# SCH_timer555_2026-08-26.net
KiCad netlist of a schematic drawn in EasyEDA
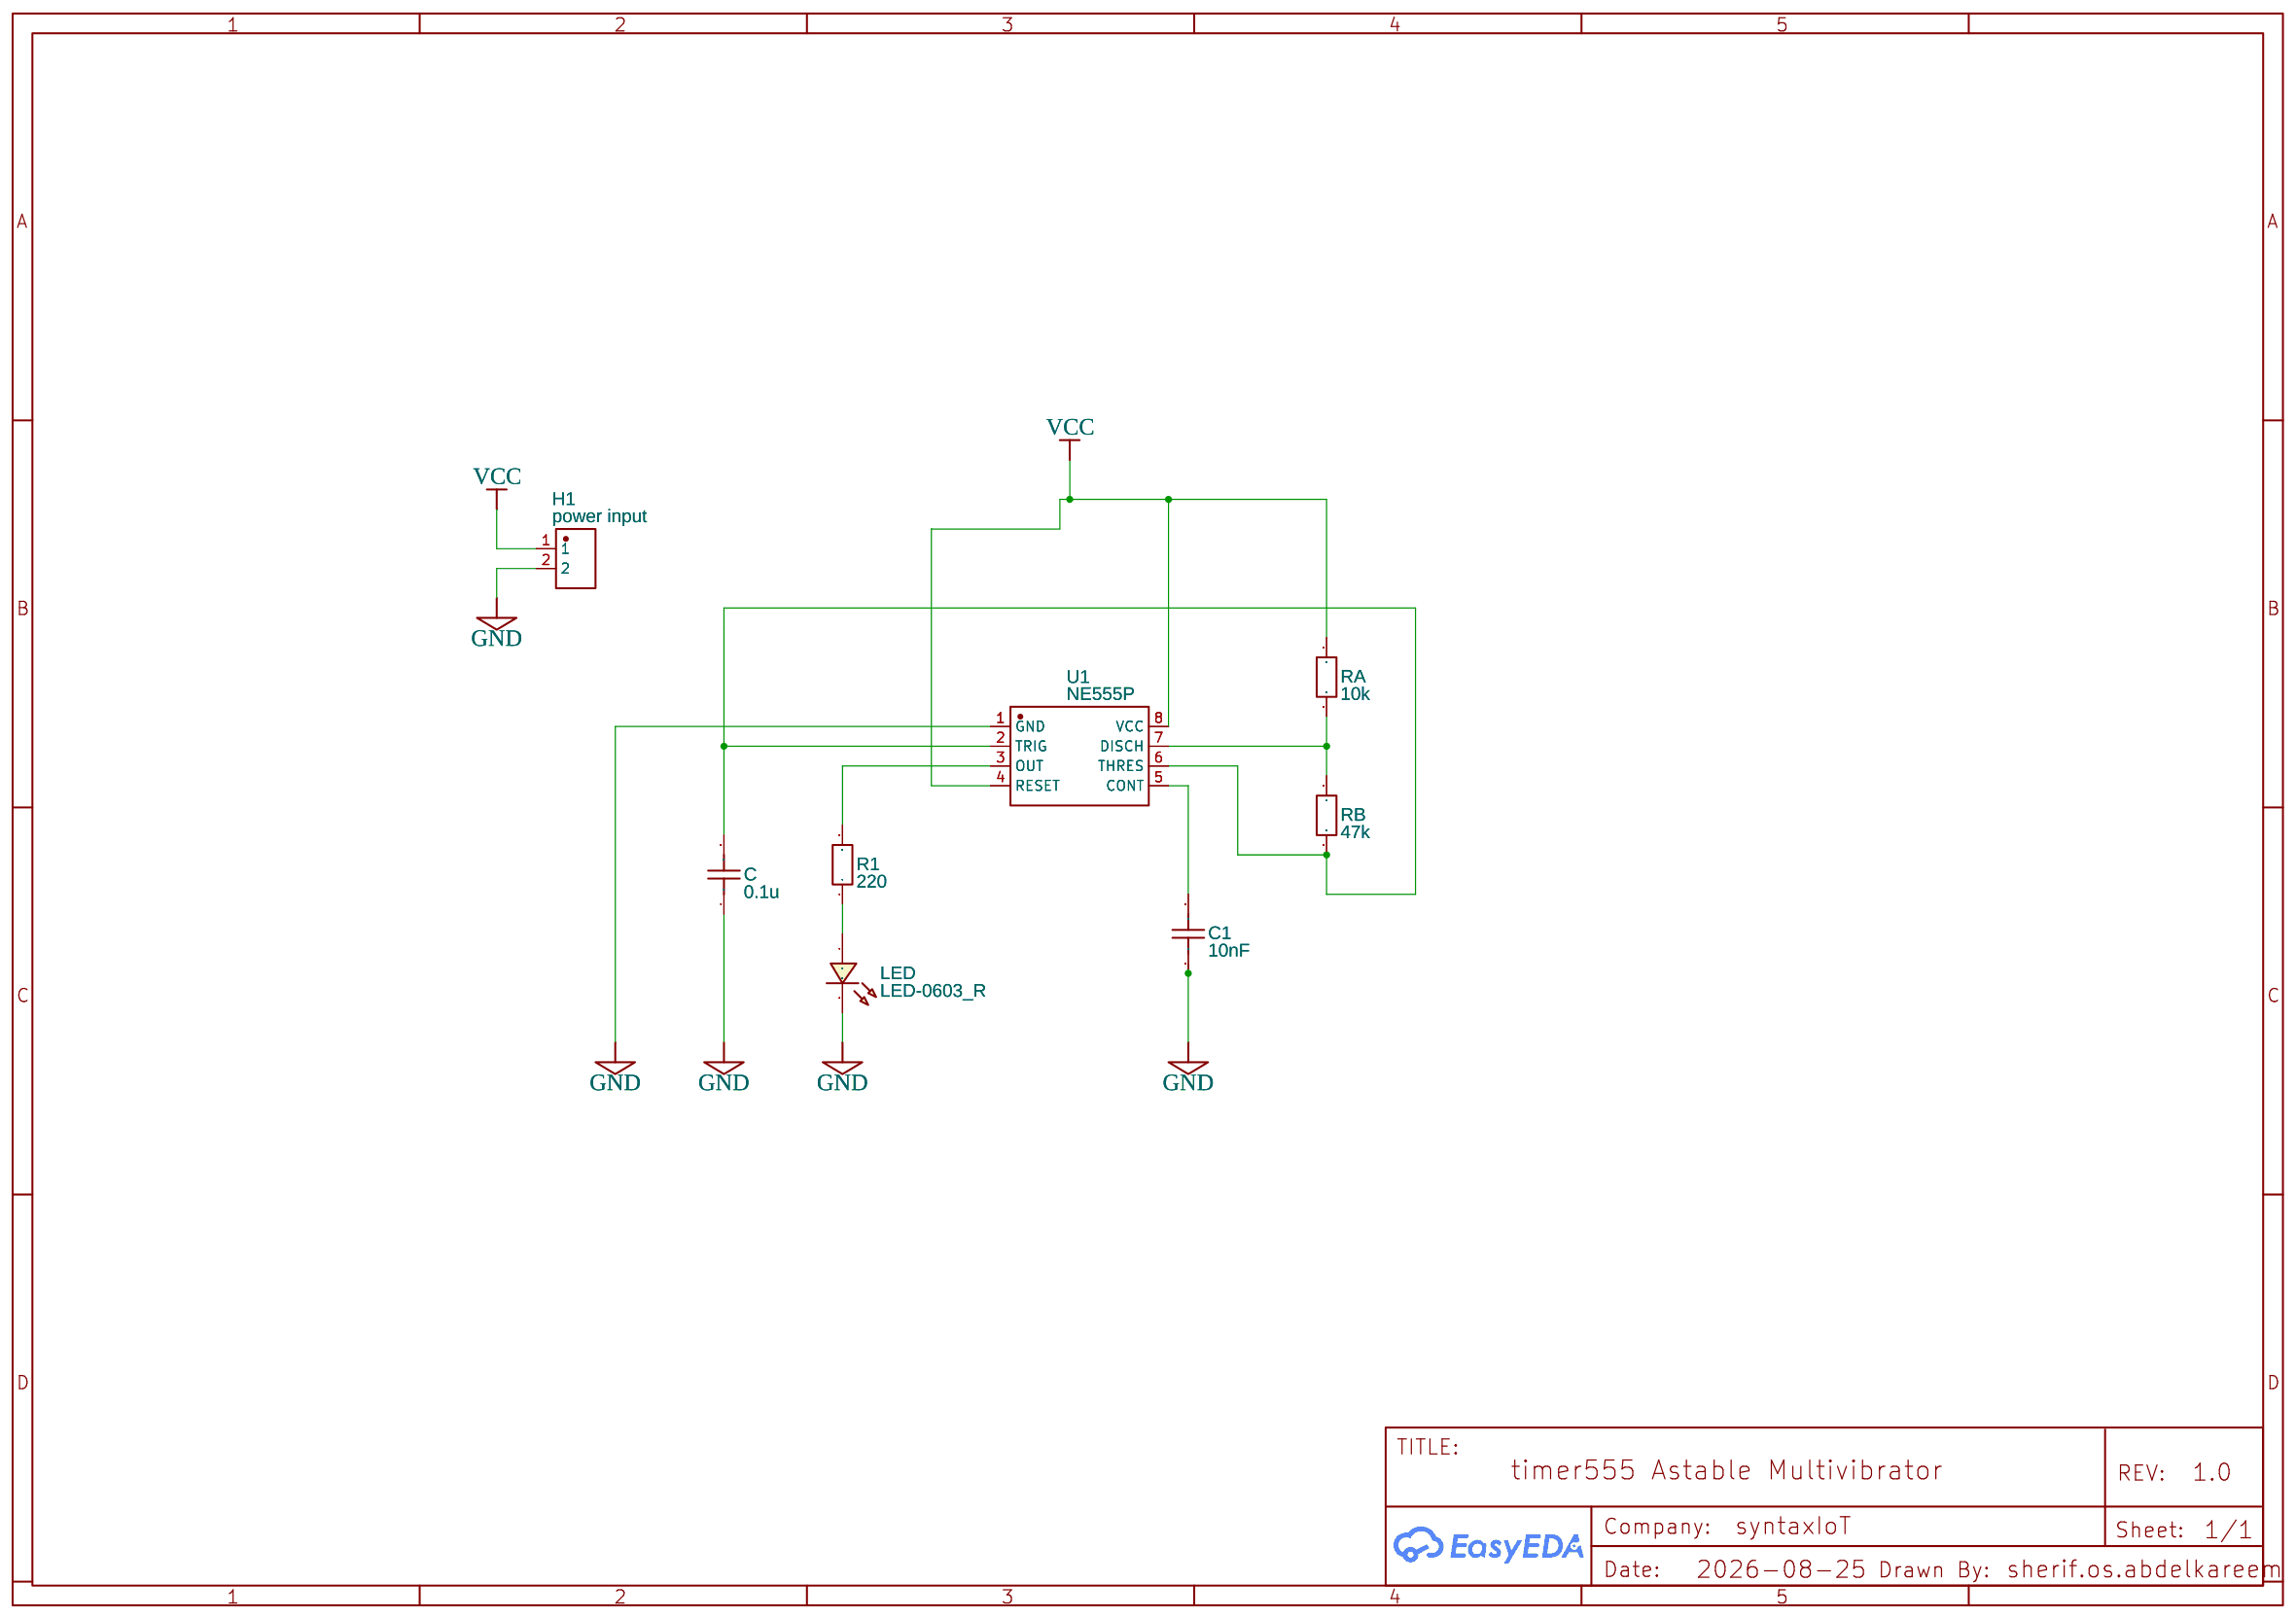
[diagram p0: schematic sheet]

(export (version "E")
  (design (tool "Eeschema 10.0.6"))
  (components
    (comp (ref "C") (value "0.1u") (libsource (lib "") (part "C_0603_US")))
    (comp (ref "C1") (value "10nF") (libsource (lib "") (part "C_0603_US_1")))
    (comp (ref "H1")
      (value "power input")
      (fields
        (field (name "Manufacturer Part") "PZ-2.54-1*02-8.5-WZ")
        (field (name "Manufacturer") "BXCONN(宝讯)")
      )
      (libsource (lib "") (part "PZ-2.54-1*02-8.5-WZ"))
    )
    (comp (ref "LED")
      (value "LED-0603_R")
      (fields
        (field (name "Manufacturer Part") "19-217/R6C-AL1M2VY/3T")
        (field (name "Manufacturer") "EVERLIGHT(台湾亿光)")
      )
      (libsource (lib "") (part "LED-0603_R"))
    )
    (comp (ref "R1") (value "220") (libsource (lib "") (part "R_0603_EU_1")))
    (comp (ref "RA") (value "10k") (libsource (lib "") (part "R_0603_EU")))
    (comp (ref "RB") (value "47k") (libsource (lib "") (part "R_0603_EU_2")))
    (comp (ref "U1")
      (value "NE555P")
      (fields (field (name "Manufacturer") "TI(德州仪器)"))
      (libsource (lib "") (part "NE555P"))
    )
  )
  (nets
    (net (code "1") (name "GND") (class "Default")
      (node (ref "C") (pin "1") (pinfunction "1_1") (pintype "unspecified"))
      (node (ref "C1") (pin "2") (pinfunction "2_2") (pintype "unspecified"))
      (node (ref "H1") (pin "2") (pinfunction "2_2") (pintype "unspecified"))
      (node (ref "LED") (pin "2") (pinfunction "2_2") (pintype "unspecified"))
      (node (ref "U1") (pin "1") (pinfunction "GND_1") (pintype "unspecified"))
    )
    (net (code "2") (name "Net-(LED-Pad1)") (class "Default")
      (node (ref "LED") (pin "1") (pinfunction "1_1") (pintype "unspecified"))
      (node (ref "R1") (pin "1") (pinfunction "1_1") (pintype "unspecified"))
    )
    (net (code "3") (name "Net-(U1-CONT)") (class "Default")
      (node (ref "C1") (pin "1") (pinfunction "1_1") (pintype "unspecified"))
      (node (ref "U1") (pin "5") (pinfunction "CONT_5") (pintype "unspecified"))
    )
    (net (code "4") (name "Net-(U1-DISCH)") (class "Default")
      (node (ref "RA") (pin "2") (pinfunction "2_2") (pintype "unspecified"))
      (node (ref "RB") (pin "1") (pinfunction "1_1") (pintype "unspecified"))
      (node (ref "U1") (pin "7") (pinfunction "DISCH_7") (pintype "unspecified"))
    )
    (net (code "5") (name "Net-(U1-OUT)") (class "Default")
      (node (ref "R1") (pin "2") (pinfunction "2_2") (pintype "unspecified"))
      (node (ref "U1") (pin "3") (pinfunction "OUT_3") (pintype "unspecified"))
    )
    (net (code "6") (name "Net-(U1-THRES)") (class "Default")
      (node (ref "C") (pin "2") (pinfunction "2_2") (pintype "unspecified"))
      (node (ref "RB") (pin "2") (pinfunction "2_2") (pintype "unspecified"))
      (node (ref "U1") (pin "2") (pinfunction "TRIG_2") (pintype "unspecified"))
      (node (ref "U1") (pin "6") (pinfunction "THRES_6") (pintype "unspecified"))
    )
    (net (code "7") (name "VCC") (class "Default")
      (node (ref "H1") (pin "1") (pinfunction "1_1") (pintype "unspecified"))
      (node (ref "RA") (pin "1") (pinfunction "1_1") (pintype "unspecified"))
      (node (ref "U1") (pin "4") (pinfunction "RESET_4") (pintype "unspecified"))
      (node (ref "U1") (pin "8") (pinfunction "VCC_8") (pintype "unspecified"))
    )
  )
)
